# Industrial_Switcher.net
KiCad netlist of a schematic drawn in EAGLE
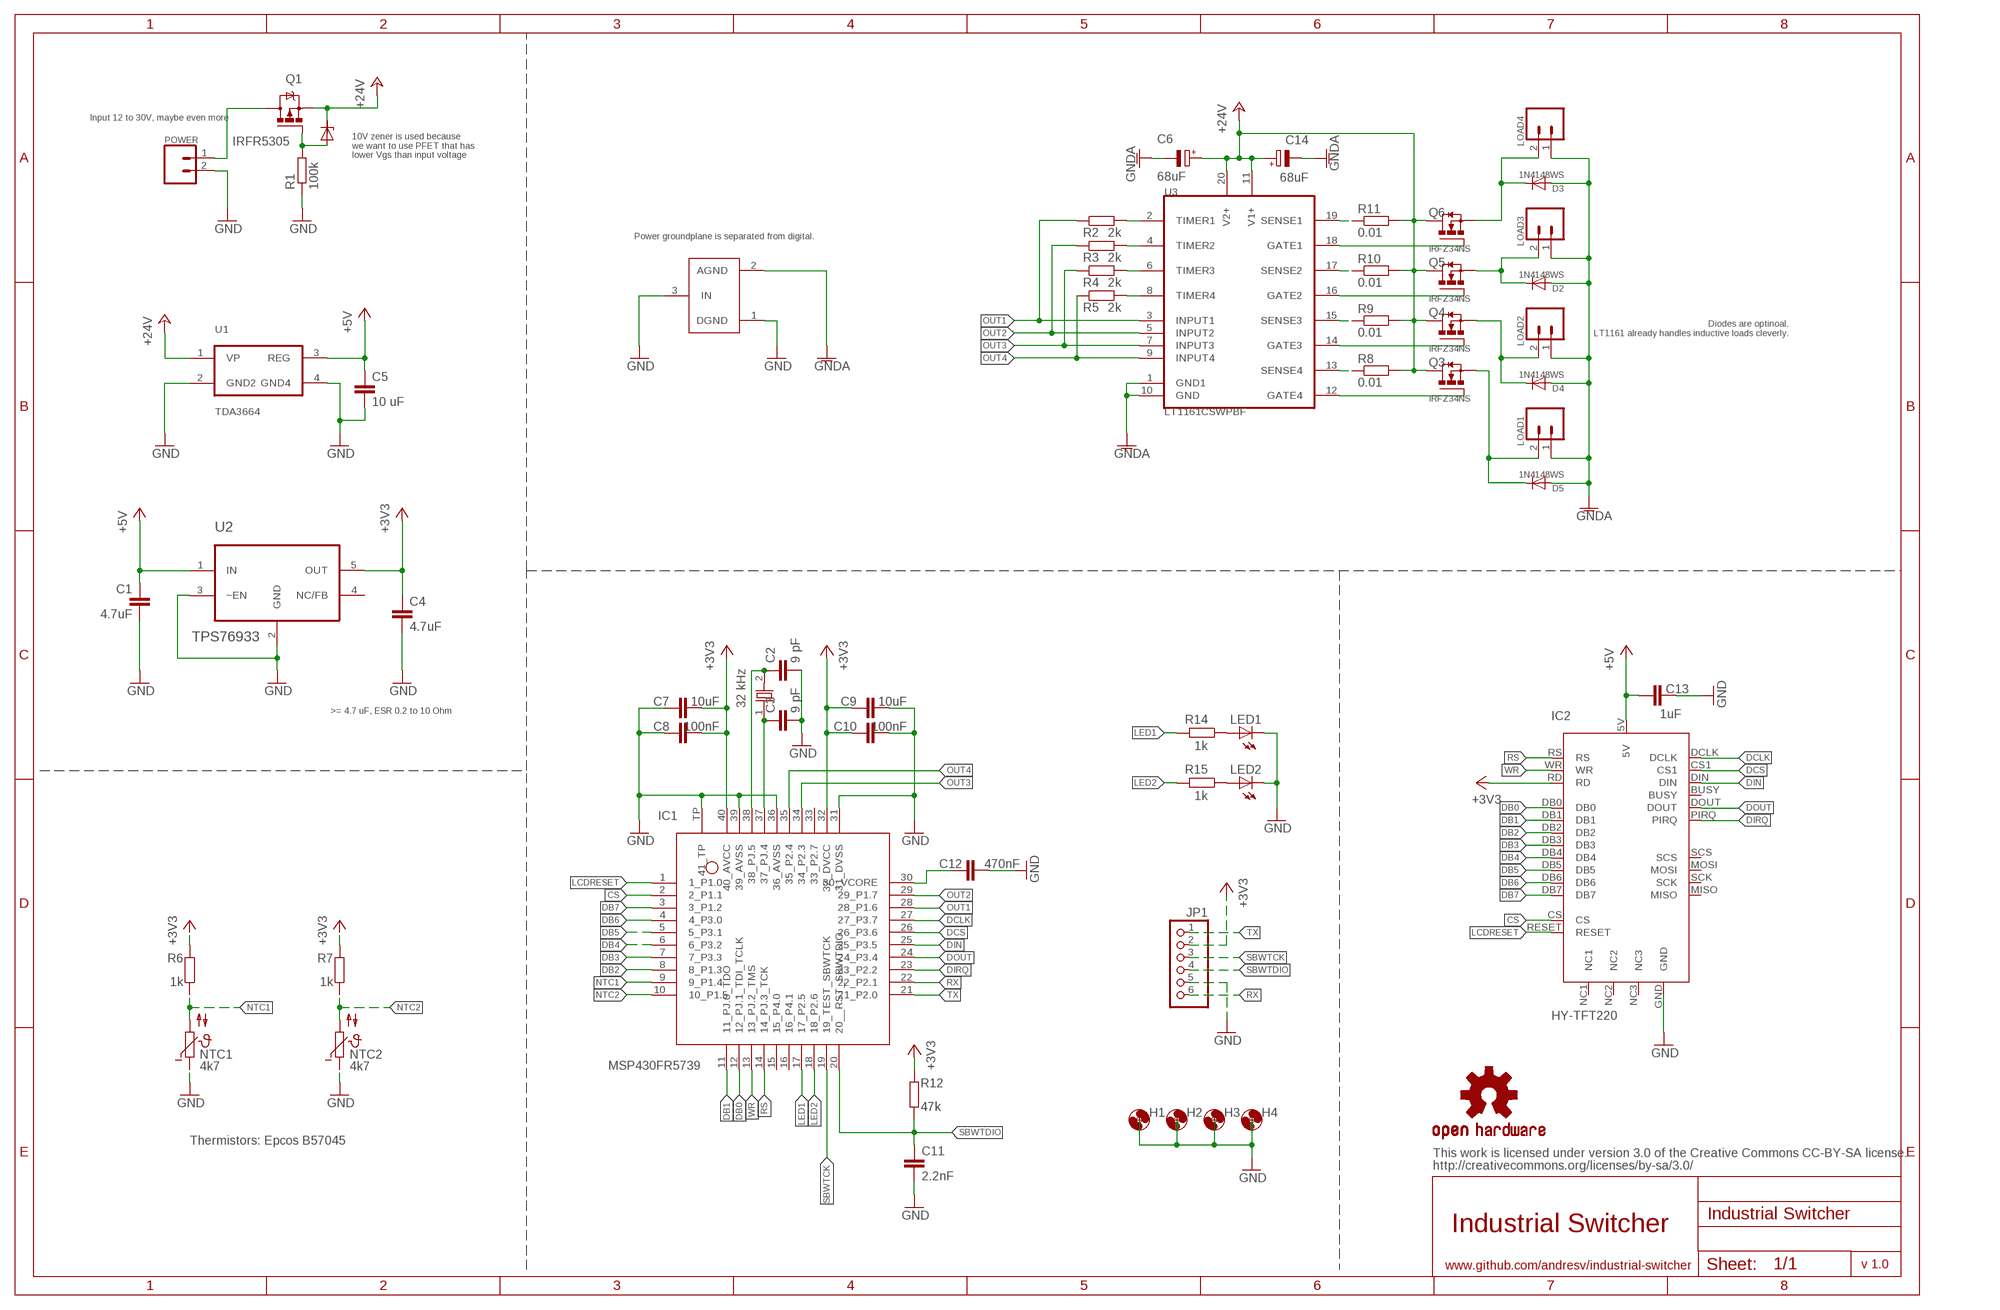
[diagram p0: schematic, sheet 1]

(export (version "E")
  (design (tool "Eeschema 10.0.6"))
  (components
    (comp (ref "C1")
      (value "4.7uF")
      (footprint "eagle-import:C0805")
      (libsource (lib "eagle-import") (part "C-EUC0805"))
    )
    (comp (ref "C2")
      (value "9 pF")
      (footprint "eagle-import:C0402")
      (libsource (lib "eagle-import") (part "C-EUC0402"))
    )
    (comp (ref "C3")
      (value "9 pF")
      (footprint "eagle-import:C0402")
      (libsource (lib "eagle-import") (part "C-EUC0402"))
    )
    (comp (ref "C4")
      (value "4.7uF")
      (footprint "eagle-import:C1206")
      (libsource (lib "eagle-import") (part "C-EUC1206"))
    )
    (comp (ref "C5")
      (value "10 uF")
      (footprint "eagle-import:C1206")
      (libsource (lib "eagle-import") (part "C-EUC1206"))
    )
    (comp (ref "C6")
      (value "68uF")
      (footprint "eagle-import:PANASONIC_F")
      (libsource (lib "eagle-import") (part "CPOL-EUF"))
    )
    (comp (ref "C7")
      (value "10uF")
      (footprint "eagle-import:C0603")
      (libsource (lib "eagle-import") (part "C-EUC0603"))
    )
    (comp (ref "C8")
      (value "100nF")
      (footprint "eagle-import:C0603")
      (libsource (lib "eagle-import") (part "C-EUC0603"))
    )
    (comp (ref "C9")
      (value "10uF")
      (footprint "eagle-import:C0603")
      (libsource (lib "eagle-import") (part "C-EUC0603"))
    )
    (comp (ref "C10")
      (value "100nF")
      (footprint "eagle-import:C0603")
      (libsource (lib "eagle-import") (part "C-EUC0603"))
    )
    (comp (ref "C11")
      (value "2.2nF")
      (footprint "eagle-import:C0402")
      (libsource (lib "eagle-import") (part "C-EUC0402"))
    )
    (comp (ref "C12")
      (value "470nF")
      (footprint "eagle-import:C0603")
      (libsource (lib "eagle-import") (part "C-EUC0603"))
    )
    (comp (ref "C13")
      (value "1uF")
      (footprint "eagle-import:C0805")
      (libsource (lib "eagle-import") (part "C-EUC0805"))
    )
    (comp (ref "C14")
      (value "68uF")
      (footprint "eagle-import:PANASONIC_F")
      (libsource (lib "eagle-import") (part "CPOL-EUF"))
    )
    (comp (ref "D1")
      (value "10V")
      (footprint "eagle-import:SOD323-W")
      (libsource (lib "eagle-import") (part "ZDIODE-SOD323"))
    )
    (comp (ref "D2")
      (value "1N4148WS")
      (footprint "eagle-import:SOD323-W")
      (libsource (lib "eagle-import") (part "DIODE-SOD323-W"))
    )
    (comp (ref "D3")
      (value "1N4148WS")
      (footprint "eagle-import:SOD323-W")
      (libsource (lib "eagle-import") (part "DIODE-SOD323-W"))
    )
    (comp (ref "D4")
      (value "1N4148WS")
      (footprint "eagle-import:SOD323-W")
      (libsource (lib "eagle-import") (part "DIODE-SOD323-W"))
    )
    (comp (ref "D5")
      (value "1N4148WS")
      (footprint "eagle-import:SOD323-W")
      (libsource (lib "eagle-import") (part "DIODE-SOD323-W"))
    )
    (comp (ref "H1")
      (value "MOUNT-HOLE3.0")
      (footprint "eagle-import:3,0")
      (libsource (lib "eagle-import") (part "MOUNT-HOLE3.0"))
    )
    (comp (ref "H2")
      (value "MOUNT-HOLE3.0")
      (footprint "eagle-import:3,0")
      (libsource (lib "eagle-import") (part "MOUNT-HOLE3.0"))
    )
    (comp (ref "H3")
      (value "MOUNT-HOLE3.0")
      (footprint "eagle-import:3,0")
      (libsource (lib "eagle-import") (part "MOUNT-HOLE3.0"))
    )
    (comp (ref "H4")
      (value "MOUNT-HOLE3.0")
      (footprint "eagle-import:3,0")
      (libsource (lib "eagle-import") (part "MOUNT-HOLE3.0"))
    )
    (comp (ref "IC1")
      (value "MSP430FR5739")
      (footprint "eagle-import:RHA40")
      (libsource (lib "eagle-import") (part "FR57XX--RHA40RHAPACKAGE"))
    )
    (comp (ref "IC2")
      (value "HY-TFT220")
      (footprint "eagle-import:2.2TFT")
      (libsource (lib "eagle-import") (part "2.2TFT"))
    )
    (comp (ref "JP1")
      (value "PINHD-1X6")
      (footprint "eagle-import:1X06")
      (libsource (lib "eagle-import") (part "PINHD-1X6"))
    )
    (comp (ref "LED1")
      (value "LEDCHIP-LED0603")
      (footprint "eagle-import:CHIP-LED0603")
      (libsource (lib "eagle-import") (part "LEDCHIP-LED0603"))
    )
    (comp (ref "LED2")
      (value "LEDCHIP-LED0603")
      (footprint "eagle-import:CHIP-LED0603")
      (libsource (lib "eagle-import") (part "LEDCHIP-LED0603"))
    )
    (comp (ref "LOAD1")
      (value "M025MM")
      (footprint "eagle-import:SCREWTERMINAL-5MM-2")
      (libsource (lib "eagle-import") (part "M025MM"))
    )
    (comp (ref "LOAD2")
      (value "M025MM")
      (footprint "eagle-import:SCREWTERMINAL-5MM-2")
      (libsource (lib "eagle-import") (part "M025MM"))
    )
    (comp (ref "LOAD3")
      (value "M025MM")
      (footprint "eagle-import:SCREWTERMINAL-5MM-2")
      (libsource (lib "eagle-import") (part "M025MM"))
    )
    (comp (ref "LOAD4")
      (value "M025MM")
      (footprint "eagle-import:SCREWTERMINAL-5MM-2")
      (libsource (lib "eagle-import") (part "M025MM"))
    )
    (comp (ref "LOGO2")
      (value "OSHW-LOGOL")
      (footprint "eagle-import:OSHW-LOGO-L")
      (libsource (lib "eagle-import") (part "OSHW-LOGOL"))
    )
    (comp (ref "NTC1")
      (value "4k7")
      (footprint "eagle-import:N640")
      (libsource (lib "eagle-import") (part "NTC640-9"))
    )
    (comp (ref "NTC2")
      (value "4k7")
      (footprint "eagle-import:N640")
      (libsource (lib "eagle-import") (part "NTC640-9"))
    )
    (comp (ref "POWER")
      (value "M025MM")
      (footprint "eagle-import:SCREWTERMINAL-5MM-2")
      (libsource (lib "eagle-import") (part "M025MM"))
    )
    (comp (ref "Q1")
      (value "IRFR5305")
      (footprint "eagle-import:D-PAK_TO252AA")
      (libsource (lib "eagle-import") (part "IRF?5305R"))
    )
    (comp (ref "Q2")
      (value "32 kHz")
      (footprint "eagle-import:ABS07")
      (libsource (lib "eagle-import") (part "ABS07"))
    )
    (comp (ref "Q3")
      (value "IRFZ34NS")
      (footprint "eagle-import:D2PACK")
      (libsource (lib "eagle-import") (part "IRF3704S"))
    )
    (comp (ref "Q4")
      (value "IRFZ34NS")
      (footprint "eagle-import:D2PACK")
      (libsource (lib "eagle-import") (part "IRF3704S"))
    )
    (comp (ref "Q5")
      (value "IRFZ34NS")
      (footprint "eagle-import:D2PACK")
      (libsource (lib "eagle-import") (part "IRF3704S"))
    )
    (comp (ref "Q6")
      (value "IRFZ34NS")
      (footprint "eagle-import:D2PACK")
      (libsource (lib "eagle-import") (part "IRF3704S"))
    )
    (comp (ref "R1")
      (value "100k")
      (footprint "eagle-import:R0603")
      (libsource (lib "eagle-import") (part "R-EU_R0603"))
    )
    (comp (ref "R2")
      (value "2k")
      (footprint "eagle-import:R0603")
      (libsource (lib "eagle-import") (part "R-EU_R0603"))
    )
    (comp (ref "R3")
      (value "2k")
      (footprint "eagle-import:R0603")
      (libsource (lib "eagle-import") (part "R-EU_R0603"))
    )
    (comp (ref "R4")
      (value "2k")
      (footprint "eagle-import:R0603")
      (libsource (lib "eagle-import") (part "R-EU_R0603"))
    )
    (comp (ref "R5")
      (value "2k")
      (footprint "eagle-import:R0603")
      (libsource (lib "eagle-import") (part "R-EU_R0603"))
    )
    (comp (ref "R6")
      (value "1k")
      (footprint "eagle-import:R0603")
      (libsource (lib "eagle-import") (part "R-EU_R0603"))
    )
    (comp (ref "R7")
      (value "1k")
      (footprint "eagle-import:R0603")
      (libsource (lib "eagle-import") (part "R-EU_R0603"))
    )
    (comp (ref "R8")
      (value "0.01")
      (footprint "eagle-import:R0603")
      (libsource (lib "eagle-import") (part "R-EU_R0603"))
    )
    (comp (ref "R9")
      (value "0.01")
      (footprint "eagle-import:R0603")
      (libsource (lib "eagle-import") (part "R-EU_R0603"))
    )
    (comp (ref "R10")
      (value "0.01")
      (footprint "eagle-import:R0603")
      (libsource (lib "eagle-import") (part "R-EU_R0603"))
    )
    (comp (ref "R11")
      (value "0.01")
      (footprint "eagle-import:R0603")
      (libsource (lib "eagle-import") (part "R-EU_R0603"))
    )
    (comp (ref "R12")
      (value "47k")
      (footprint "eagle-import:R0402")
      (libsource (lib "eagle-import") (part "R-EU_R0402"))
    )
    (comp (ref "R14")
      (value "1k")
      (footprint "eagle-import:R0402")
      (libsource (lib "eagle-import") (part "R-EU_R0402"))
    )
    (comp (ref "R15")
      (value "1k")
      (footprint "eagle-import:R0402")
      (libsource (lib "eagle-import") (part "R-EU_R0402"))
    )
    (comp (ref "U$1")
      (value "GND_CONNECT")
      (footprint "eagle-import:GND_CONNECT")
      (libsource (lib "eagle-import") (part "GND_CONNECT"))
    )
    (comp (ref "U1")
      (value "TDA3664")
      (footprint "eagle-import:DRFRIEDPARTS_DOAAZ")
      (libsource (lib "eagle-import") (part "295-TDA3664/N1,135"))
    )
    (comp (ref "U2")
      (value "TPS76933")
      (footprint "eagle-import:SOT95P280X145-5N")
      (fields (field (name "MPN") "TPS76933DBVT"))
      (libsource (lib "eagle-import") (part "TPS76933DBVT"))
    )
    (comp (ref "U3")
      (value "LT1161CSWPBF")
      (footprint "eagle-import:ANDRESV_B3JU7")
      (libsource (lib "eagle-import") (part "337-LT1161CSWPBF"))
    )
  )
  (nets
    (net (code "1") (name "+3V3") (class "Default")
      (node (ref "C10") (pin "1") (pinfunction "1_1") (pintype "passive"))
      (node (ref "C4") (pin "1") (pinfunction "1_1") (pintype "passive"))
      (node (ref "C7") (pin "2") (pinfunction "2_2") (pintype "passive"))
      (node (ref "C8") (pin "2") (pinfunction "2_2") (pintype "passive"))
      (node (ref "C9") (pin "1") (pinfunction "1_1") (pintype "passive"))
      (node (ref "IC1") (pin "32") (pinfunction "32_DVCC_32") (pintype "passive"))
      (node (ref "IC1") (pin "40") (pinfunction "40_AVCC_40") (pintype "passive"))
      (node (ref "IC2") (pin "RD") (pinfunction "RD_RD") (pintype "bidirectional"))
      (node (ref "JP1") (pin "2") (pinfunction "2_2") (pintype "passive"))
      (node (ref "R12") (pin "2") (pinfunction "2_2") (pintype "passive"))
      (node (ref "R6") (pin "2") (pinfunction "2_2") (pintype "passive"))
      (node (ref "R7") (pin "2") (pinfunction "2_2") (pintype "passive"))
      (node (ref "U2") (pin "5") (pinfunction "OUT_5") (pintype "output"))
    )
    (net (code "2") (name "+5V") (class "Default")
      (node (ref "C1") (pin "1") (pinfunction "1_1") (pintype "passive"))
      (node (ref "C13") (pin "2") (pinfunction "2_2") (pintype "passive"))
      (node (ref "C5") (pin "1") (pinfunction "1_1") (pintype "passive"))
      (node (ref "IC2") (pin "5V") (pinfunction "5V_5V") (pintype "bidirectional"))
      (node (ref "U1") (pin "3") (pinfunction "REG_3") (pintype "input"))
      (node (ref "U2") (pin "1") (pinfunction "IN_1") (pintype "power_in"))
    )
    (net (code "3") (name "+24V") (class "Default")
      (node (ref "C14") (pin "+") (pinfunction "+_+") (pintype "passive"))
      (node (ref "C6") (pin "+") (pinfunction "+_+") (pintype "passive"))
      (node (ref "D1") (pin "C") (pinfunction "C_C") (pintype "bidirectional"))
      (node (ref "Q1") (pin "3") (pinfunction "S_3") (pintype "passive"))
      (node (ref "Q3") (pin "2") (pinfunction "D_2") (pintype "passive"))
      (node (ref "Q4") (pin "2") (pinfunction "D_2") (pintype "passive"))
      (node (ref "Q5") (pin "2") (pinfunction "D_2") (pintype "passive"))
      (node (ref "Q6") (pin "2") (pinfunction "D_2") (pintype "passive"))
      (node (ref "R10") (pin "2") (pinfunction "2_2") (pintype "passive"))
      (node (ref "R11") (pin "2") (pinfunction "2_2") (pintype "passive"))
      (node (ref "R8") (pin "2") (pinfunction "2_2") (pintype "passive"))
      (node (ref "R9") (pin "2") (pinfunction "2_2") (pintype "passive"))
      (node (ref "U1") (pin "1") (pinfunction "VP_1") (pintype "input"))
      (node (ref "U3") (pin "11") (pinfunction "V1+_11") (pintype "input"))
      (node (ref "U3") (pin "20") (pinfunction "V2+_20") (pintype "input"))
    )
    (net (code "4") (name "CS") (class "Default")
      (node (ref "IC1") (pin "2") (pinfunction "2_P1.1_2") (pintype "passive"))
      (node (ref "IC2") (pin "CS") (pinfunction "CS_CS") (pintype "bidirectional"))
    )
    (net (code "5") (name "DB0") (class "Default")
      (node (ref "IC1") (pin "12") (pinfunction "12_PJ.1_TDI_TCLK_12") (pintype "passive"))
      (node (ref "IC2") (pin "DB0") (pinfunction "DB0_DB0") (pintype "bidirectional"))
    )
    (net (code "6") (name "DB1") (class "Default")
      (node (ref "IC1") (pin "11") (pinfunction "11_PJ.0_TDO_11") (pintype "passive"))
      (node (ref "IC2") (pin "DB1") (pinfunction "DB1_DB1") (pintype "bidirectional"))
    )
    (net (code "7") (name "DB2") (class "Default")
      (node (ref "IC1") (pin "8") (pinfunction "8_P1.3_8") (pintype "passive"))
      (node (ref "IC2") (pin "DB2") (pinfunction "DB2_DB2") (pintype "bidirectional"))
    )
    (net (code "8") (name "DB3") (class "Default")
      (node (ref "IC1") (pin "7") (pinfunction "7_P3.3_7") (pintype "passive"))
      (node (ref "IC2") (pin "DB3") (pinfunction "DB3_DB3") (pintype "bidirectional"))
    )
    (net (code "9") (name "DB4") (class "Default")
      (node (ref "IC1") (pin "6") (pinfunction "6_P3.2_6") (pintype "passive"))
      (node (ref "IC2") (pin "DB4") (pinfunction "DB4_DB4") (pintype "bidirectional"))
    )
    (net (code "10") (name "DB5") (class "Default")
      (node (ref "IC1") (pin "5") (pinfunction "5_P3.1_5") (pintype "passive"))
      (node (ref "IC2") (pin "DB5") (pinfunction "DB5_DB5") (pintype "bidirectional"))
    )
    (net (code "11") (name "DB6") (class "Default")
      (node (ref "IC1") (pin "4") (pinfunction "4_P3.0_4") (pintype "passive"))
      (node (ref "IC2") (pin "DB6") (pinfunction "DB6_DB6") (pintype "bidirectional"))
    )
    (net (code "12") (name "DB7") (class "Default")
      (node (ref "IC1") (pin "3") (pinfunction "3_P1.2_3") (pintype "passive"))
      (node (ref "IC2") (pin "DB7") (pinfunction "DB7_DB7") (pintype "bidirectional"))
    )
    (net (code "13") (name "DCLK") (class "Default")
      (node (ref "IC1") (pin "27") (pinfunction "27_P3.7_27") (pintype "passive"))
      (node (ref "IC2") (pin "DCLK") (pinfunction "DCLK_DCLK") (pintype "bidirectional"))
    )
    (net (code "14") (name "DCS") (class "Default")
      (node (ref "IC1") (pin "26") (pinfunction "26_P3.6_26") (pintype "passive"))
      (node (ref "IC2") (pin "CS1") (pinfunction "CS1_CS1") (pintype "bidirectional"))
    )
    (net (code "15") (name "DIN") (class "Default")
      (node (ref "IC1") (pin "25") (pinfunction "25_P3.5_25") (pintype "passive"))
      (node (ref "IC2") (pin "DIN") (pinfunction "DIN_DIN") (pintype "bidirectional"))
    )
    (net (code "16") (name "DIRQ") (class "Default")
      (node (ref "IC1") (pin "23") (pinfunction "23_P2.2_23") (pintype "passive"))
      (node (ref "IC2") (pin "PIRQ") (pinfunction "PIRQ_PIRQ") (pintype "bidirectional"))
    )
    (net (code "17") (name "DOUT") (class "Default")
      (node (ref "IC1") (pin "24") (pinfunction "24_P3.4_24") (pintype "passive"))
      (node (ref "IC2") (pin "DOUT") (pinfunction "DOUT_DOUT") (pintype "bidirectional"))
    )
    (net (code "18") (name "GND") (class "Default")
      (node (ref "C1") (pin "2") (pinfunction "2_2") (pintype "passive"))
      (node (ref "C10") (pin "2") (pinfunction "2_2") (pintype "passive"))
      (node (ref "C11") (pin "2") (pinfunction "2_2") (pintype "passive"))
      (node (ref "C12") (pin "2") (pinfunction "2_2") (pintype "passive"))
      (node (ref "C13") (pin "1") (pinfunction "1_1") (pintype "passive"))
      (node (ref "C2") (pin "2") (pinfunction "2_2") (pintype "passive"))
      (node (ref "C3") (pin "2") (pinfunction "2_2") (pintype "passive"))
      (node (ref "C4") (pin "2") (pinfunction "2_2") (pintype "passive"))
      (node (ref "C5") (pin "2") (pinfunction "2_2") (pintype "passive"))
      (node (ref "C7") (pin "1") (pinfunction "1_1") (pintype "passive"))
      (node (ref "C8") (pin "1") (pinfunction "1_1") (pintype "passive"))
      (node (ref "C9") (pin "2") (pinfunction "2_2") (pintype "passive"))
      (node (ref "IC1") (pin "31") (pinfunction "31_DVSS_31") (pintype "passive"))
      (node (ref "IC1") (pin "36") (pinfunction "36_AVSS_36") (pintype "passive"))
      (node (ref "IC1") (pin "39") (pinfunction "39_AVSS_39") (pintype "passive"))
      (node (ref "IC1") (pin "TP") (pinfunction "41_TP_TP") (pintype "passive"))
      (node (ref "IC2") (pin "GND") (pinfunction "GND_GND") (pintype "bidirectional"))
      (node (ref "JP1") (pin "5") (pinfunction "5_5") (pintype "passive"))
      (node (ref "LED1") (pin "C") (pinfunction "C_C") (pintype "passive"))
      (node (ref "LED2") (pin "C") (pinfunction "C_C") (pintype "passive"))
      (node (ref "NTC1") (pin "1") (pinfunction "1_1") (pintype "passive"))
      (node (ref "NTC2") (pin "1") (pinfunction "1_1") (pintype "passive"))
      (node (ref "POWER") (pin "2") (pinfunction "2_2") (pintype "passive"))
      (node (ref "R1") (pin "1") (pinfunction "1_1") (pintype "passive"))
      (node (ref "U$1") (pin "1") (pinfunction "DGND_1") (pintype "bidirectional"))
      (node (ref "U$1") (pin "3") (pinfunction "IN_3") (pintype "bidirectional"))
      (node (ref "U1") (pin "2") (pinfunction "GND2_2") (pintype "input"))
      (node (ref "U1") (pin "4") (pinfunction "GND4_4") (pintype "input"))
      (node (ref "U2") (pin "2") (pinfunction "GND_2") (pintype "passive"))
      (node (ref "U2") (pin "3") (pinfunction "~{EN}_3") (pintype "input"))
    )
    (net (code "19") (name "GNDA") (class "Default")
      (node (ref "C14") (pin "-") (pinfunction "-_-") (pintype "passive"))
      (node (ref "C6") (pin "-") (pinfunction "-_-") (pintype "passive"))
      (node (ref "D2") (pin "A") (pinfunction "A_A") (pintype "passive"))
      (node (ref "D3") (pin "A") (pinfunction "A_A") (pintype "passive"))
      (node (ref "D4") (pin "A") (pinfunction "A_A") (pintype "passive"))
      (node (ref "D5") (pin "A") (pinfunction "A_A") (pintype "passive"))
      (node (ref "LOAD1") (pin "1") (pinfunction "1_1") (pintype "passive"))
      (node (ref "LOAD2") (pin "1") (pinfunction "1_1") (pintype "passive"))
      (node (ref "LOAD3") (pin "1") (pinfunction "1_1") (pintype "passive"))
      (node (ref "LOAD4") (pin "1") (pinfunction "1_1") (pintype "passive"))
      (node (ref "U$1") (pin "2") (pinfunction "AGND_2") (pintype "bidirectional"))
      (node (ref "U3") (pin "1") (pinfunction "GND1_1") (pintype "input"))
      (node (ref "U3") (pin "10") (pinfunction "GND_10") (pintype "input"))
    )
    (net (code "20") (name "LCDRESET") (class "Default")
      (node (ref "IC1") (pin "1") (pinfunction "1_P1.0_1") (pintype "passive"))
      (node (ref "IC2") (pin "RESET") (pinfunction "RESET_RESET") (pintype "bidirectional"))
    )
    (net (code "21") (name "LED1") (class "Default")
      (node (ref "IC1") (pin "17") (pinfunction "17_P2.5_17") (pintype "passive"))
      (node (ref "R14") (pin "2") (pinfunction "2_2") (pintype "passive"))
    )
    (net (code "22") (name "LED2") (class "Default")
      (node (ref "IC1") (pin "18") (pinfunction "18_P2.6_18") (pintype "passive"))
      (node (ref "R15") (pin "2") (pinfunction "2_2") (pintype "passive"))
    )
    (net (code "23") (name "NTC1") (class "Default")
      (node (ref "IC1") (pin "9") (pinfunction "9_P1.4_9") (pintype "passive"))
      (node (ref "NTC1") (pin "2") (pinfunction "2_2") (pintype "passive"))
      (node (ref "R6") (pin "1") (pinfunction "1_1") (pintype "passive"))
    )
    (net (code "24") (name "NTC2") (class "Default")
      (node (ref "IC1") (pin "10") (pinfunction "10_P1.5_10") (pintype "passive"))
      (node (ref "NTC2") (pin "2") (pinfunction "2_2") (pintype "passive"))
      (node (ref "R7") (pin "1") (pinfunction "1_1") (pintype "passive"))
    )
    (net (code "25") (name "Net-(IC1-30_VCORE)") (class "Default")
      (node (ref "C12") (pin "1") (pinfunction "1_1") (pintype "passive"))
      (node (ref "IC1") (pin "30") (pinfunction "30_VCORE_30") (pintype "passive"))
    )
    (net (code "26") (name "Net-(IC1-37_PJ.4)") (class "Default")
      (node (ref "C3") (pin "1") (pinfunction "1_1") (pintype "passive"))
      (node (ref "IC1") (pin "37") (pinfunction "37_PJ.4_37") (pintype "passive"))
      (node (ref "Q2") (pin "1") (pinfunction "1_1") (pintype "passive"))
    )
    (net (code "27") (name "Net-(IC1-38_PJ.5)") (class "Default")
      (node (ref "C2") (pin "1") (pinfunction "1_1") (pintype "passive"))
      (node (ref "IC1") (pin "38") (pinfunction "38_PJ.5_38") (pintype "passive"))
      (node (ref "Q2") (pin "2") (pinfunction "2_2") (pintype "passive"))
    )
    (net (code "28") (name "Net-(LED1-PadA)") (class "Default")
      (node (ref "LED1") (pin "A") (pinfunction "A_A") (pintype "passive"))
      (node (ref "R14") (pin "1") (pinfunction "1_1") (pintype "passive"))
    )
    (net (code "29") (name "Net-(LED2-PadA)") (class "Default")
      (node (ref "LED2") (pin "A") (pinfunction "A_A") (pintype "passive"))
      (node (ref "R15") (pin "1") (pinfunction "1_1") (pintype "passive"))
    )
    (net (code "30") (name "Net-(Q1-D)") (class "Default")
      (node (ref "POWER") (pin "1") (pinfunction "1_1") (pintype "passive"))
      (node (ref "Q1") (pin "4") (pinfunction "D_4") (pintype "passive"))
    )
    (net (code "31") (name "Net-(Q1-G)") (class "Default")
      (node (ref "D1") (pin "A") (pinfunction "A_A") (pintype "bidirectional"))
      (node (ref "Q1") (pin "1") (pinfunction "G_1") (pintype "passive"))
      (node (ref "R1") (pin "2") (pinfunction "2_2") (pintype "passive"))
    )
    (net (code "32") (name "Net-(Q3-G)") (class "Default")
      (node (ref "Q3") (pin "1") (pinfunction "G_1") (pintype "passive"))
      (node (ref "U3") (pin "12") (pinfunction "GATE4_12") (pintype "input"))
    )
    (net (code "33") (name "Net-(Q3-S)") (class "Default")
      (node (ref "D5") (pin "C") (pinfunction "C_C") (pintype "passive"))
      (node (ref "LOAD1") (pin "2") (pinfunction "2_2") (pintype "passive"))
      (node (ref "Q3") (pin "3") (pinfunction "S_3") (pintype "passive"))
    )
    (net (code "34") (name "Net-(Q4-G)") (class "Default")
      (node (ref "Q4") (pin "1") (pinfunction "G_1") (pintype "passive"))
      (node (ref "U3") (pin "14") (pinfunction "GATE3_14") (pintype "input"))
    )
    (net (code "35") (name "Net-(Q4-S)") (class "Default")
      (node (ref "D4") (pin "C") (pinfunction "C_C") (pintype "passive"))
      (node (ref "LOAD2") (pin "2") (pinfunction "2_2") (pintype "passive"))
      (node (ref "Q4") (pin "3") (pinfunction "S_3") (pintype "passive"))
    )
    (net (code "36") (name "Net-(Q5-G)") (class "Default")
      (node (ref "Q5") (pin "1") (pinfunction "G_1") (pintype "passive"))
      (node (ref "U3") (pin "16") (pinfunction "GATE2_16") (pintype "input"))
    )
    (net (code "37") (name "Net-(Q5-S)") (class "Default")
      (node (ref "D2") (pin "C") (pinfunction "C_C") (pintype "passive"))
      (node (ref "LOAD3") (pin "2") (pinfunction "2_2") (pintype "passive"))
      (node (ref "Q5") (pin "3") (pinfunction "S_3") (pintype "passive"))
    )
    (net (code "38") (name "Net-(Q6-G)") (class "Default")
      (node (ref "Q6") (pin "1") (pinfunction "G_1") (pintype "passive"))
      (node (ref "U3") (pin "18") (pinfunction "GATE1_18") (pintype "input"))
    )
    (net (code "39") (name "Net-(Q6-S)") (class "Default")
      (node (ref "D3") (pin "C") (pinfunction "C_C") (pintype "passive"))
      (node (ref "LOAD4") (pin "2") (pinfunction "2_2") (pintype "passive"))
      (node (ref "Q6") (pin "3") (pinfunction "S_3") (pintype "passive"))
    )
    (net (code "40") (name "Net-(U3-SENSE1)") (class "Default")
      (node (ref "R11") (pin "1") (pinfunction "1_1") (pintype "passive"))
      (node (ref "U3") (pin "19") (pinfunction "SENSE1_19") (pintype "input"))
    )
    (net (code "41") (name "Net-(U3-SENSE2)") (class "Default")
      (node (ref "R10") (pin "1") (pinfunction "1_1") (pintype "passive"))
      (node (ref "U3") (pin "17") (pinfunction "SENSE2_17") (pintype "input"))
    )
    (net (code "42") (name "Net-(U3-SENSE3)") (class "Default")
      (node (ref "R9") (pin "1") (pinfunction "1_1") (pintype "passive"))
      (node (ref "U3") (pin "15") (pinfunction "SENSE3_15") (pintype "input"))
    )
    (net (code "43") (name "Net-(U3-SENSE4)") (class "Default")
      (node (ref "R8") (pin "1") (pinfunction "1_1") (pintype "passive"))
      (node (ref "U3") (pin "13") (pinfunction "SENSE4_13") (pintype "input"))
    )
    (net (code "44") (name "Net-(U3-TIMER1)") (class "Default")
      (node (ref "R2") (pin "2") (pinfunction "2_2") (pintype "passive"))
      (node (ref "U3") (pin "2") (pinfunction "TIMER1_2") (pintype "input"))
    )
    (net (code "45") (name "Net-(U3-TIMER2)") (class "Default")
      (node (ref "R3") (pin "2") (pinfunction "2_2") (pintype "passive"))
      (node (ref "U3") (pin "4") (pinfunction "TIMER2_4") (pintype "input"))
    )
    (net (code "46") (name "Net-(U3-TIMER3)") (class "Default")
      (node (ref "R4") (pin "2") (pinfunction "2_2") (pintype "passive"))
      (node (ref "U3") (pin "6") (pinfunction "TIMER3_6") (pintype "input"))
    )
    (net (code "47") (name "Net-(U3-TIMER4)") (class "Default")
      (node (ref "R5") (pin "2") (pinfunction "2_2") (pintype "passive"))
      (node (ref "U3") (pin "8") (pinfunction "TIMER4_8") (pintype "input"))
    )
    (net (code "48") (name "OUT1") (class "Default")
      (node (ref "IC1") (pin "28") (pinfunction "28_P1.6_28") (pintype "passive"))
      (node (ref "R2") (pin "1") (pinfunction "1_1") (pintype "passive"))
      (node (ref "U3") (pin "3") (pinfunction "INPUT1_3") (pintype "input"))
    )
    (net (code "49") (name "OUT2") (class "Default")
      (node (ref "IC1") (pin "29") (pinfunction "29_P1.7_29") (pintype "passive"))
      (node (ref "R3") (pin "1") (pinfunction "1_1") (pintype "passive"))
      (node (ref "U3") (pin "5") (pinfunction "INPUT2_5") (pintype "input"))
    )
    (net (code "50") (name "OUT3") (class "Default")
      (node (ref "IC1") (pin "34") (pinfunction "34_P2.3_34") (pintype "passive"))
      (node (ref "R4") (pin "1") (pinfunction "1_1") (pintype "passive"))
      (node (ref "U3") (pin "7") (pinfunction "INPUT3_7") (pintype "input"))
    )
    (net (code "51") (name "OUT4") (class "Default")
      (node (ref "IC1") (pin "35") (pinfunction "35_P2.4_35") (pintype "passive"))
      (node (ref "R5") (pin "1") (pinfunction "1_1") (pintype "passive"))
      (node (ref "U3") (pin "9") (pinfunction "INPUT4_9") (pintype "input"))
    )
    (net (code "52") (name "RS") (class "Default")
      (node (ref "IC1") (pin "14") (pinfunction "14_PJ.3_TCK_14") (pintype "passive"))
      (node (ref "IC2") (pin "RS") (pinfunction "RS_RS") (pintype "bidirectional"))
    )
    (net (code "53") (name "RX") (class "Default")
      (node (ref "IC1") (pin "22") (pinfunction "22_P2.1_22") (pintype "passive"))
      (node (ref "JP1") (pin "6") (pinfunction "6_6") (pintype "passive"))
    )
    (net (code "54") (name "SBWTCK") (class "Default")
      (node (ref "IC1") (pin "19") (pinfunction "19_TEST_SBWTCK_19") (pintype "passive"))
      (node (ref "JP1") (pin "3") (pinfunction "3_3") (pintype "passive"))
    )
    (net (code "55") (name "SBWTDIO") (class "Default")
      (node (ref "C11") (pin "1") (pinfunction "1_1") (pintype "passive"))
      (node (ref "IC1") (pin "20") (pinfunction "20__RST_SBWTDIO_20") (pintype "passive"))
      (node (ref "JP1") (pin "4") (pinfunction "4_4") (pintype "passive"))
      (node (ref "R12") (pin "1") (pinfunction "1_1") (pintype "passive"))
    )
    (net (code "56") (name "TX") (class "Default")
      (node (ref "IC1") (pin "21") (pinfunction "21_P2.0_21") (pintype "passive"))
      (node (ref "JP1") (pin "1") (pinfunction "1_1") (pintype "passive"))
    )
    (net (code "57") (name "WR") (class "Default")
      (node (ref "IC1") (pin "13") (pinfunction "13_PJ.2_TMS_13") (pintype "passive"))
      (node (ref "IC2") (pin "WR") (pinfunction "WR_WR") (pintype "bidirectional"))
    )
    (net (code "58") (name "unconnected-(IC1-15_P4.0-Pad15)") (class "Default")
      (node (ref "IC1") (pin "15") (pinfunction "15_P4.0_15") (pintype "passive"))
    )
    (net (code "59") (name "unconnected-(IC1-16_P4.1-Pad16)") (class "Default")
      (node (ref "IC1") (pin "16") (pinfunction "16_P4.1_16") (pintype "passive"))
    )
    (net (code "60") (name "unconnected-(IC1-33_P2.7-Pad33)") (class "Default")
      (node (ref "IC1") (pin "33") (pinfunction "33_P2.7_33") (pintype "passive"))
    )
    (net (code "61") (name "unconnected-(IC2-PadBUSY)") (class "Default")
      (node (ref "IC2") (pin "BUSY") (pinfunction "BUSY_BUSY") (pintype "bidirectional"))
    )
    (net (code "62") (name "unconnected-(IC2-PadMISO)") (class "Default")
      (node (ref "IC2") (pin "MISO") (pinfunction "MISO_MISO") (pintype "bidirectional"))
    )
    (net (code "63") (name "unconnected-(IC2-PadMOSI)") (class "Default")
      (node (ref "IC2") (pin "MOSI") (pinfunction "MOSI_MOSI") (pintype "bidirectional"))
    )
    (net (code "64") (name "unconnected-(IC2-PadNC1)") (class "Default")
      (node (ref "IC2") (pin "NC1") (pinfunction "NC1_NC1") (pintype "bidirectional"))
    )
    (net (code "65") (name "unconnected-(IC2-PadNC2)") (class "Default")
      (node (ref "IC2") (pin "NC2") (pinfunction "NC2_NC2") (pintype "bidirectional"))
    )
    (net (code "66") (name "unconnected-(IC2-PadNC3)") (class "Default")
      (node (ref "IC2") (pin "NC3") (pinfunction "NC3_NC3") (pintype "bidirectional"))
    )
    (net (code "67") (name "unconnected-(IC2-PadSCK)") (class "Default")
      (node (ref "IC2") (pin "SCK") (pinfunction "SCK_SCK") (pintype "bidirectional"))
    )
    (net (code "68") (name "unconnected-(IC2-PadSCS)") (class "Default")
      (node (ref "IC2") (pin "SCS") (pinfunction "SCS_SCS") (pintype "bidirectional"))
    )
    (net (code "69") (name "unconnected-(U2-NC{slash}FB-Pad4)") (class "Default")
      (node (ref "U2") (pin "4") (pinfunction "NC/FB_4") (pintype "passive"))
    )
  )
)
